# LMS7_FE.net
KiCad netlist of a schematic drawn in Altium Designer
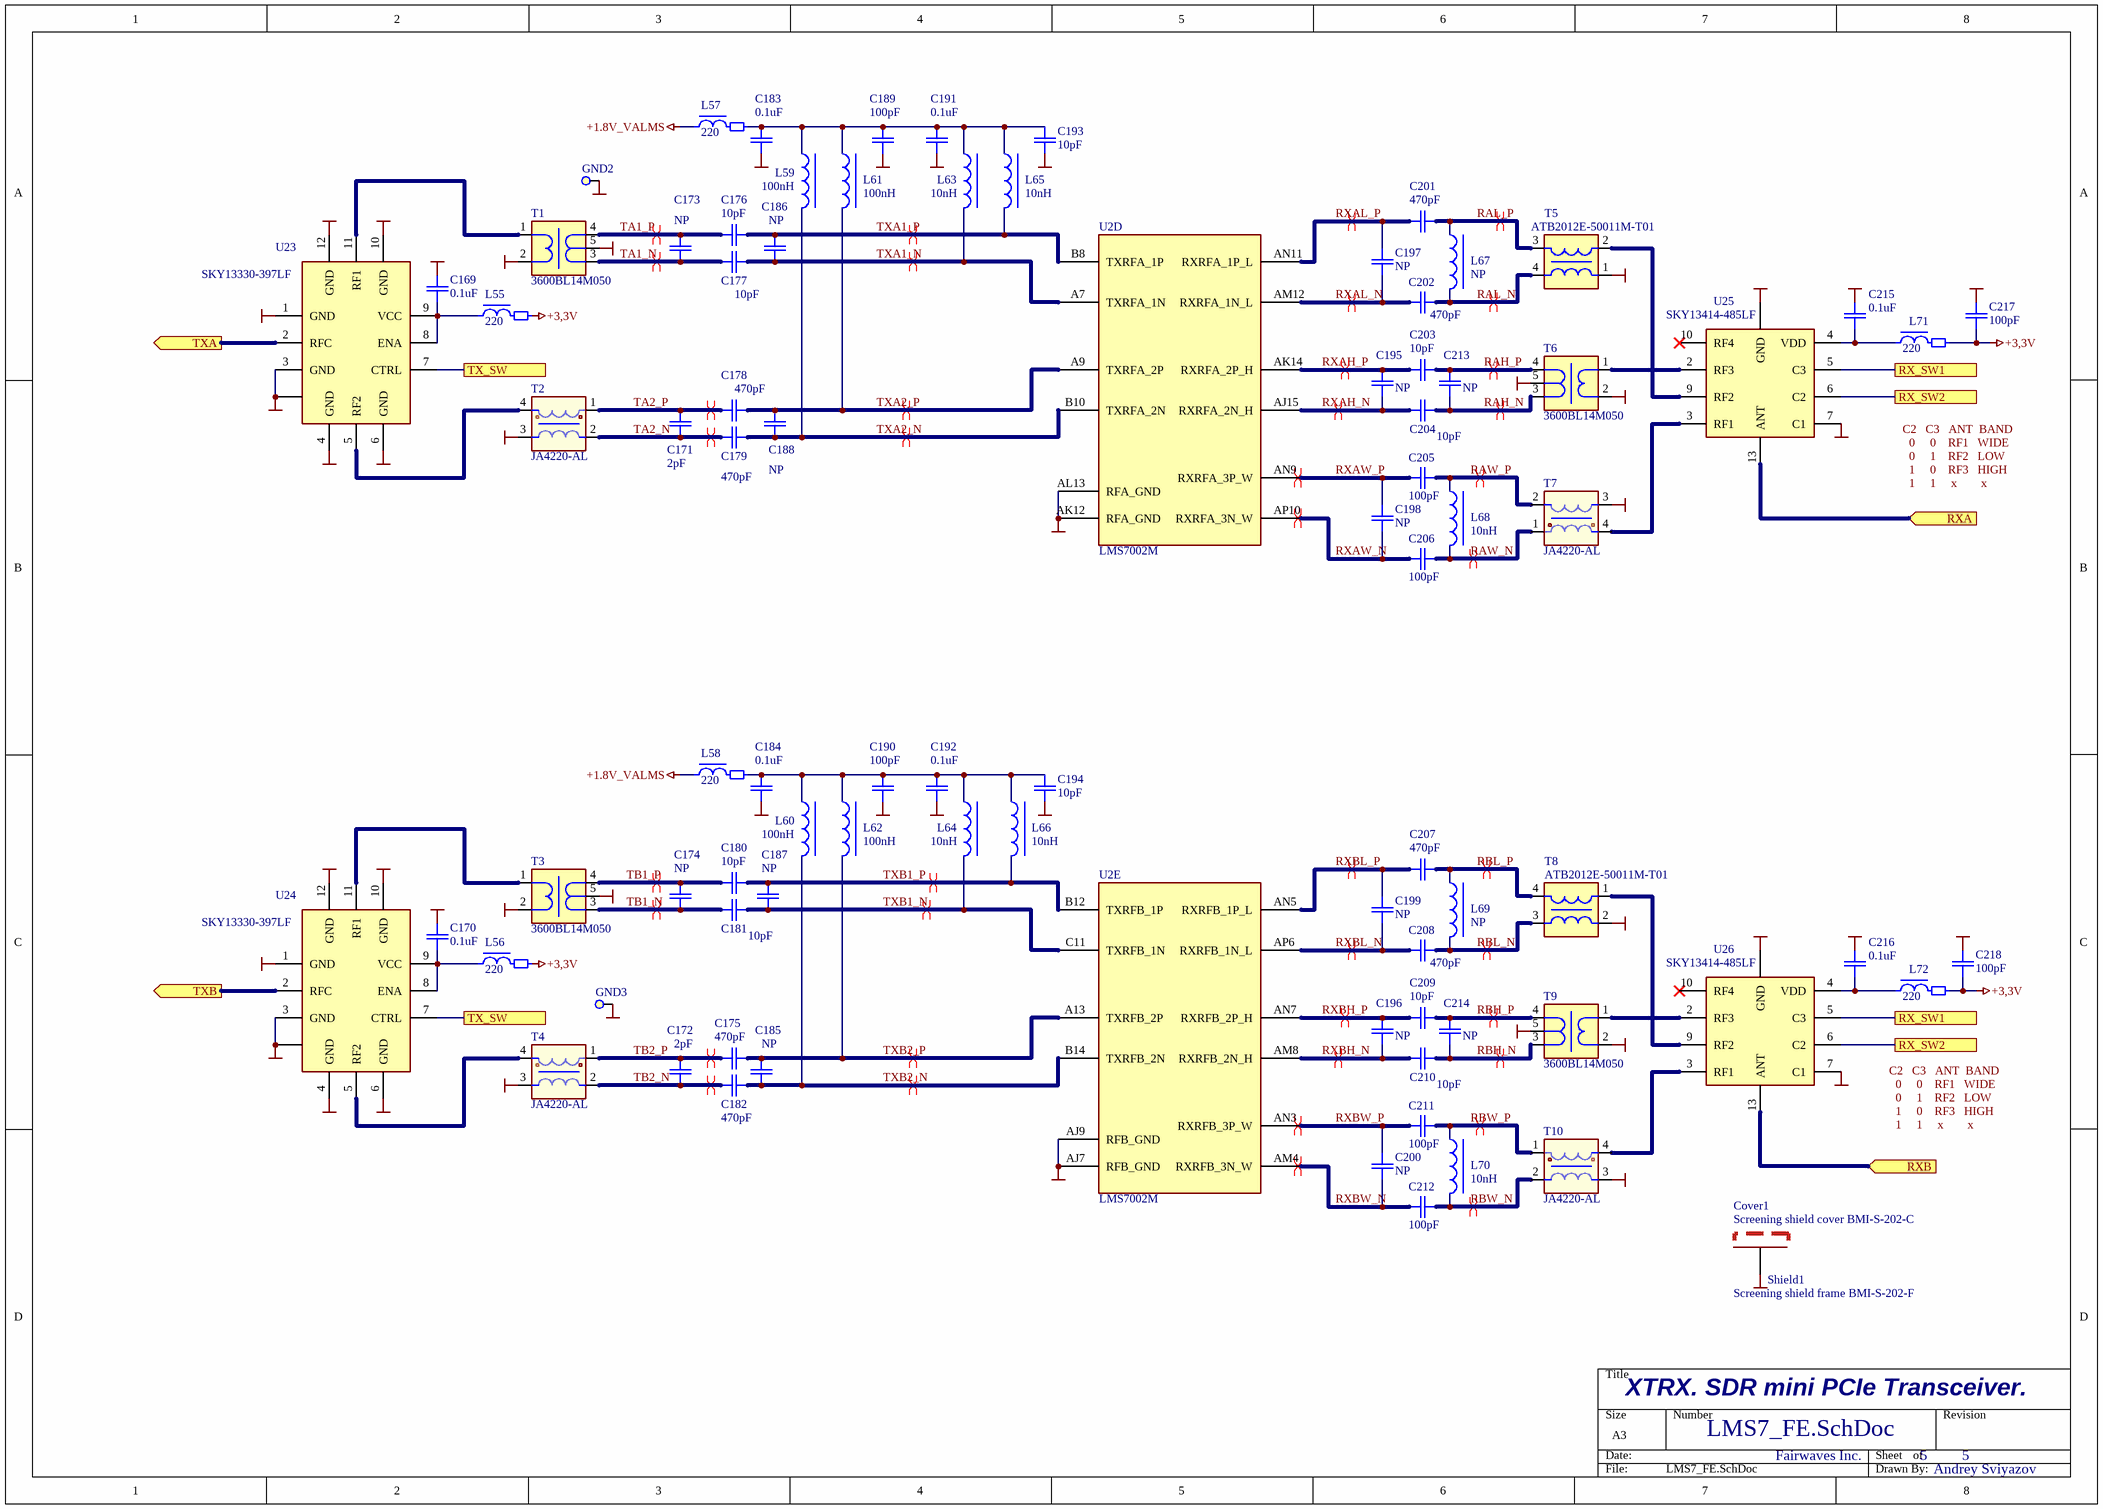
[diagram p0: LMS7_FE.SchDoc]

(export (version "E")
  (design (tool "Eeschema 10.0.6"))
  (components
    (comp (ref "C169")
      (value "0.1uF")
      (footprint "C0402-cirq")
      (description "Capacitor")
      (fields (field (name "MANUFACTURER") "Any") (field (name "TOLERANCE") "20%"))
      (libsource (lib "Capacitors") (part "C0402"))
    )
    (comp (ref "C170")
      (value "0.1uF")
      (footprint "C0402-cirq")
      (description "Capacitor")
      (fields (field (name "MANUFACTURER") "Any") (field (name "TOLERANCE") "20%"))
      (libsource (lib "Capacitors") (part "C0402"))
    )
    (comp (ref "C171")
      (value "2pF")
      (footprint "C0402-cirq")
      (description "Capacitor")
      (fields (field (name "MANUFACTURER") "Any") (field (name "TOLERANCE") "10%"))
      (libsource (lib "Capacitors") (part "C0402"))
    )
    (comp (ref "C172")
      (value "2pF")
      (footprint "C0402-cirq")
      (description "Capacitor")
      (fields (field (name "MANUFACTURER") "Any") (field (name "TOLERANCE") "10%"))
      (libsource (lib "Capacitors") (part "C0402"))
    )
    (comp (ref "C173")
      (value "NP")
      (footprint "C0402-cirq")
      (description "Capacitor")
      (fields (field (name "MANUFACTURER") "MURATA") (field (name "TOLERANCE") "20%"))
      (libsource (lib "Capacitors") (part "C0402"))
    )
    (comp (ref "C174")
      (value "NP")
      (footprint "C0402-cirq")
      (description "Capacitor")
      (fields (field (name "MANUFACTURER") "MURATA") (field (name "TOLERANCE") "20%"))
      (libsource (lib "Capacitors") (part "C0402"))
    )
    (comp (ref "C175")
      (value "470pF")
      (footprint "C0402-cirq")
      (description "Capacitor")
      (fields (field (name "MANUFACTURER") "Any") (field (name "TOLERANCE") "20%"))
      (libsource (lib "Capacitors") (part "C0402"))
    )
    (comp (ref "C176")
      (value "10pF")
      (footprint "C0402-cirq")
      (description "Capacitor")
      (fields (field (name "MANUFACTURER") "Any") (field (name "TOLERANCE") "20%"))
      (libsource (lib "Capacitors") (part "C0402"))
    )
    (comp (ref "C177")
      (value "10pF")
      (footprint "C0402-cirq")
      (description "Capacitor")
      (fields (field (name "MANUFACTURER") "Any") (field (name "TOLERANCE") "20%"))
      (libsource (lib "Capacitors") (part "C0402"))
    )
    (comp (ref "C178")
      (value "470pF")
      (footprint "C0402-cirq")
      (description "Capacitor")
      (fields (field (name "MANUFACTURER") "Any") (field (name "TOLERANCE") "20%"))
      (libsource (lib "Capacitors") (part "C0402"))
    )
    (comp (ref "C179")
      (value "470pF")
      (footprint "C0402-cirq")
      (description "Capacitor")
      (fields (field (name "MANUFACTURER") "Any") (field (name "TOLERANCE") "20%"))
      (libsource (lib "Capacitors") (part "C0402"))
    )
    (comp (ref "C180")
      (value "10pF")
      (footprint "C0402-cirq")
      (description "Capacitor")
      (fields (field (name "MANUFACTURER") "Any") (field (name "TOLERANCE") "20%"))
      (libsource (lib "Capacitors") (part "C0402"))
    )
    (comp (ref "C181")
      (value "10pF")
      (footprint "C0402-cirq")
      (description "Capacitor")
      (fields (field (name "MANUFACTURER") "Any") (field (name "TOLERANCE") "20%"))
      (libsource (lib "Capacitors") (part "C0402"))
    )
    (comp (ref "C182")
      (value "470pF")
      (footprint "C0402-cirq")
      (description "Capacitor")
      (fields (field (name "MANUFACTURER") "Any") (field (name "TOLERANCE") "20%"))
      (libsource (lib "Capacitors") (part "C0402"))
    )
    (comp (ref "C183")
      (value "0.1uF")
      (footprint "C0402-cirq")
      (description "Capacitor")
      (fields (field (name "MANUFACTURER") "Any") (field (name "TOLERANCE") "20%"))
      (libsource (lib "Capacitors") (part "C0402"))
    )
    (comp (ref "C184")
      (value "0.1uF")
      (footprint "C0402-cirq")
      (description "Capacitor")
      (fields (field (name "MANUFACTURER") "Any") (field (name "TOLERANCE") "20%"))
      (libsource (lib "Capacitors") (part "C0402"))
    )
    (comp (ref "C185")
      (value "NP")
      (footprint "C0402-cirq")
      (description "Capacitor")
      (fields (field (name "MANUFACTURER") "MURATA") (field (name "TOLERANCE") "20%"))
      (libsource (lib "Capacitors") (part "C0402"))
    )
    (comp (ref "C186")
      (value "NP")
      (footprint "C0402-cirq")
      (description "Capacitor")
      (fields (field (name "MANUFACTURER") "MURATA") (field (name "TOLERANCE") "20%"))
      (libsource (lib "Capacitors") (part "C0402"))
    )
    (comp (ref "C187")
      (value "NP")
      (footprint "C0402-cirq")
      (description "Capacitor")
      (fields (field (name "MANUFACTURER") "MURATA") (field (name "TOLERANCE") "20%"))
      (libsource (lib "Capacitors") (part "C0402"))
    )
    (comp (ref "C188")
      (value "NP")
      (footprint "C0402-cirq")
      (description "Capacitor")
      (fields (field (name "MANUFACTURER") "MURATA") (field (name "TOLERANCE") "20%"))
      (libsource (lib "Capacitors") (part "C0402"))
    )
    (comp (ref "C189")
      (value "100pF")
      (footprint "C0402-cirq")
      (description "Capacitor")
      (fields (field (name "MANUFACTURER") "Any") (field (name "TOLERANCE") "20%"))
      (libsource (lib "Capacitors") (part "C0402"))
    )
    (comp (ref "C190")
      (value "100pF")
      (footprint "C0402-cirq")
      (description "Capacitor")
      (fields (field (name "MANUFACTURER") "Any") (field (name "TOLERANCE") "20%"))
      (libsource (lib "Capacitors") (part "C0402"))
    )
    (comp (ref "C191")
      (value "0.1uF")
      (footprint "C0402-cirq")
      (description "Capacitor")
      (fields (field (name "MANUFACTURER") "Any") (field (name "TOLERANCE") "20%"))
      (libsource (lib "Capacitors") (part "C0402"))
    )
    (comp (ref "C192")
      (value "0.1uF")
      (footprint "C0402-cirq")
      (description "Capacitor")
      (fields (field (name "MANUFACTURER") "Any") (field (name "TOLERANCE") "20%"))
      (libsource (lib "Capacitors") (part "C0402"))
    )
    (comp (ref "C193")
      (value "10pF")
      (footprint "C0402-cirq")
      (description "Capacitor")
      (fields (field (name "MANUFACTURER") "Any") (field (name "TOLERANCE") "20%"))
      (libsource (lib "Capacitors") (part "C0402"))
    )
    (comp (ref "C194")
      (value "10pF")
      (footprint "C0402-cirq")
      (description "Capacitor")
      (fields (field (name "MANUFACTURER") "Any") (field (name "TOLERANCE") "20%"))
      (libsource (lib "Capacitors") (part "C0402"))
    )
    (comp (ref "C195")
      (value "NP")
      (footprint "C0402-cirq")
      (description "Capacitor")
      (fields (field (name "MANUFACTURER") "MURATA") (field (name "TOLERANCE") "20%"))
      (libsource (lib "Capacitors") (part "C0402"))
    )
    (comp (ref "C196")
      (value "NP")
      (footprint "C0402-cirq")
      (description "Capacitor")
      (fields (field (name "MANUFACTURER") "MURATA") (field (name "TOLERANCE") "20%"))
      (libsource (lib "Capacitors") (part "C0402"))
    )
    (comp (ref "C197")
      (value "NP")
      (footprint "C0402-cirq")
      (description "Capacitor")
      (fields (field (name "MANUFACTURER") "MURATA") (field (name "TOLERANCE") "20%"))
      (libsource (lib "Capacitors") (part "C0402"))
    )
    (comp (ref "C198")
      (value "NP")
      (footprint "C0402-cirq")
      (description "Capacitor")
      (fields (field (name "MANUFACTURER") "MURATA") (field (name "TOLERANCE") "20%"))
      (libsource (lib "Capacitors") (part "C0402"))
    )
    (comp (ref "C199")
      (value "NP")
      (footprint "C0402-cirq")
      (description "Capacitor")
      (fields (field (name "MANUFACTURER") "MURATA") (field (name "TOLERANCE") "20%"))
      (libsource (lib "Capacitors") (part "C0402"))
    )
    (comp (ref "C200")
      (value "NP")
      (footprint "C0402-cirq")
      (description "Capacitor")
      (fields (field (name "MANUFACTURER") "MURATA") (field (name "TOLERANCE") "20%"))
      (libsource (lib "Capacitors") (part "C0402"))
    )
    (comp (ref "C201")
      (value "470pF")
      (footprint "C0402-cirq")
      (description "Capacitor")
      (fields (field (name "MANUFACTURER") "Any") (field (name "TOLERANCE") "20%"))
      (libsource (lib "Capacitors") (part "C0402"))
    )
    (comp (ref "C202")
      (value "470pF")
      (footprint "C0402-cirq")
      (description "Capacitor")
      (fields (field (name "MANUFACTURER") "Any") (field (name "TOLERANCE") "20%"))
      (libsource (lib "Capacitors") (part "C0402"))
    )
    (comp (ref "C203")
      (value "10pF")
      (footprint "C0402-cirq")
      (description "Capacitor")
      (fields (field (name "MANUFACTURER") "Any") (field (name "TOLERANCE") "20%"))
      (libsource (lib "Capacitors") (part "C0402"))
    )
    (comp (ref "C204")
      (value "10pF")
      (footprint "C0402-cirq")
      (description "Capacitor")
      (fields (field (name "MANUFACTURER") "Any") (field (name "TOLERANCE") "20%"))
      (libsource (lib "Capacitors") (part "C0402"))
    )
    (comp (ref "C205")
      (value "100pF")
      (footprint "C0402-cirq")
      (description "Capacitor")
      (fields (field (name "MANUFACTURER") "Any") (field (name "TOLERANCE") "20%"))
      (libsource (lib "Capacitors") (part "C0402"))
    )
    (comp (ref "C206")
      (value "100pF")
      (footprint "C0402-cirq")
      (description "Capacitor")
      (fields (field (name "MANUFACTURER") "Any") (field (name "TOLERANCE") "20%"))
      (libsource (lib "Capacitors") (part "C0402"))
    )
    (comp (ref "C207")
      (value "470pF")
      (footprint "C0402-cirq")
      (description "Capacitor")
      (fields (field (name "MANUFACTURER") "Any") (field (name "TOLERANCE") "20%"))
      (libsource (lib "Capacitors") (part "C0402"))
    )
    (comp (ref "C208")
      (value "470pF")
      (footprint "C0402-cirq")
      (description "Capacitor")
      (fields (field (name "MANUFACTURER") "Any") (field (name "TOLERANCE") "20%"))
      (libsource (lib "Capacitors") (part "C0402"))
    )
    (comp (ref "C209")
      (value "10pF")
      (footprint "C0402-cirq")
      (description "Capacitor")
      (fields (field (name "MANUFACTURER") "Any") (field (name "TOLERANCE") "20%"))
      (libsource (lib "Capacitors") (part "C0402"))
    )
    (comp (ref "C210")
      (value "10pF")
      (footprint "C0402-cirq")
      (description "Capacitor")
      (fields (field (name "MANUFACTURER") "Any") (field (name "TOLERANCE") "20%"))
      (libsource (lib "Capacitors") (part "C0402"))
    )
    (comp (ref "C211")
      (value "100pF")
      (footprint "C0402-cirq")
      (description "Capacitor")
      (fields (field (name "MANUFACTURER") "Any") (field (name "TOLERANCE") "20%"))
      (libsource (lib "Capacitors") (part "C0402"))
    )
    (comp (ref "C212")
      (value "100pF")
      (footprint "C0402-cirq")
      (description "Capacitor")
      (fields (field (name "MANUFACTURER") "Any") (field (name "TOLERANCE") "20%"))
      (libsource (lib "Capacitors") (part "C0402"))
    )
    (comp (ref "C213")
      (value "NP")
      (footprint "C0402-cirq")
      (description "Capacitor")
      (fields (field (name "MANUFACTURER") "MURATA") (field (name "TOLERANCE") "20%"))
      (libsource (lib "Capacitors") (part "C0402"))
    )
    (comp (ref "C214")
      (value "NP")
      (footprint "C0402-cirq")
      (description "Capacitor")
      (fields (field (name "MANUFACTURER") "MURATA") (field (name "TOLERANCE") "20%"))
      (libsource (lib "Capacitors") (part "C0402"))
    )
    (comp (ref "C215")
      (value "0.1uF")
      (footprint "C0402-cirq")
      (description "Capacitor")
      (fields (field (name "MANUFACTURER") "Any") (field (name "TOLERANCE") "20%"))
      (libsource (lib "Capacitors") (part "C0402"))
    )
    (comp (ref "C216")
      (value "0.1uF")
      (footprint "C0402-cirq")
      (description "Capacitor")
      (fields (field (name "MANUFACTURER") "Any") (field (name "TOLERANCE") "20%"))
      (libsource (lib "Capacitors") (part "C0402"))
    )
    (comp (ref "C217")
      (value "100pF")
      (footprint "C0402-cirq")
      (description "Capacitor")
      (fields (field (name "MANUFACTURER") "Any") (field (name "TOLERANCE") "20%"))
      (libsource (lib "Capacitors") (part "C0402"))
    )
    (comp (ref "C218")
      (value "100pF")
      (footprint "C0402-cirq")
      (description "Capacitor")
      (fields (field (name "MANUFACTURER") "Any") (field (name "TOLERANCE") "20%"))
      (libsource (lib "Capacitors") (part "C0402"))
    )
    (comp (ref "Cover1")
      (value "Screening shield cover BMI-S-202-C")
      (description "Screening shield cover")
      (fields (field (name "MANUFACTURER") "Laird Tech"))
      (libsource (lib "Andy") (part "Screen cover BMI-S-202-C"))
    )
    (comp (ref "GND2")
      (value "~")
      (footprint "KP D1.5mm")
      (fields (field (name "MANUFACTURER") "PCB"))
      (libsource (lib "Connectors") (part "KP-D1.5mm"))
    )
    (comp (ref "GND3")
      (value "~")
      (footprint "KP D1.5mm")
      (fields (field (name "MANUFACTURER") "PCB"))
      (libsource (lib "Connectors") (part "KP-D1.5mm"))
    )
    (comp (ref "L55")
      (value "220")
      (footprint "BEAD0402-Phillips")
      (description "Ferrite bead EMIFIL")
      (fields (field (name "MANUFACTURER") "MURATA"))
      (libsource (lib "Andy") (part "EMI BLM15"))
    )
    (comp (ref "L56")
      (value "220")
      (footprint "BEAD0402-Phillips")
      (description "Ferrite bead EMIFIL")
      (fields (field (name "MANUFACTURER") "MURATA"))
      (libsource (lib "Andy") (part "EMI BLM15"))
    )
    (comp (ref "L57")
      (value "220")
      (footprint "BEAD0402-Phillips")
      (description "Ferrite bead EMIFIL")
      (fields (field (name "MANUFACTURER") "MURATA"))
      (libsource (lib "Andy") (part "EMI BLM15"))
    )
    (comp (ref "L58")
      (value "220")
      (footprint "BEAD0402-Phillips")
      (description "Ferrite bead EMIFIL")
      (fields (field (name "MANUFACTURER") "MURATA"))
      (libsource (lib "Andy") (part "EMI BLM15"))
    )
    (comp (ref "L59")
      (value "100nH")
      (footprint "COIL0402-Phillips")
      (description "Coil wire wound")
      (fields (field (name "MANUFACTURER") "MuRata") (field (name "TOLERANCE") "±5%"))
      (libsource (lib "Andy") (part "L-LQW15"))
    )
    (comp (ref "L60")
      (value "100nH")
      (footprint "COIL0402-Phillips")
      (description "Coil wire wound")
      (fields (field (name "MANUFACTURER") "MuRata") (field (name "TOLERANCE") "±5%"))
      (libsource (lib "Andy") (part "L-LQW15"))
    )
    (comp (ref "L61")
      (value "100nH")
      (footprint "COIL0402-Phillips")
      (description "Coil wire wound")
      (fields (field (name "MANUFACTURER") "MuRata") (field (name "TOLERANCE") "±5%"))
      (libsource (lib "Andy") (part "L-LQW15"))
    )
    (comp (ref "L62")
      (value "100nH")
      (footprint "COIL0402-Phillips")
      (description "Coil wire wound")
      (fields (field (name "MANUFACTURER") "MuRata") (field (name "TOLERANCE") "±5%"))
      (libsource (lib "Andy") (part "L-LQW15"))
    )
    (comp (ref "L63")
      (value "10nH")
      (footprint "COIL0402-Phillips")
      (description "Coil wire wound")
      (fields (field (name "MANUFACTURER") "MuRata") (field (name "TOLERANCE") "±5%"))
      (libsource (lib "Andy") (part "L-LQW15"))
    )
    (comp (ref "L64")
      (value "10nH")
      (footprint "COIL0402-Phillips")
      (description "Coil wire wound")
      (fields (field (name "MANUFACTURER") "MuRata") (field (name "TOLERANCE") "±5%"))
      (libsource (lib "Andy") (part "L-LQW15"))
    )
    (comp (ref "L65")
      (value "10nH")
      (footprint "COIL0402-Phillips")
      (description "Coil wire wound")
      (fields (field (name "MANUFACTURER") "MuRata") (field (name "TOLERANCE") "±5%"))
      (libsource (lib "Andy") (part "L-LQW15"))
    )
    (comp (ref "L66")
      (value "10nH")
      (footprint "COIL0402-Phillips")
      (description "Coil wire wound")
      (fields (field (name "MANUFACTURER") "MuRata") (field (name "TOLERANCE") "±5%"))
      (libsource (lib "Andy") (part "L-LQW15"))
    )
    (comp (ref "L67")
      (value "NP")
      (footprint "COIL0402-Phillips")
      (description "Coil wire wound")
      (fields (field (name "MANUFACTURER") "MuRata") (field (name "TOLERANCE") "±5%"))
      (libsource (lib "Andy") (part "L-LQW15"))
    )
    (comp (ref "L68")
      (value "10nH")
      (footprint "COIL0402-Phillips")
      (description "Coil wire wound")
      (fields (field (name "MANUFACTURER") "MuRata") (field (name "TOLERANCE") "±5%"))
      (libsource (lib "Andy") (part "L-LQW15"))
    )
    (comp (ref "L69")
      (value "NP")
      (footprint "COIL0402-Phillips")
      (description "Coil wire wound")
      (fields (field (name "MANUFACTURER") "MuRata") (field (name "TOLERANCE") "±5%"))
      (libsource (lib "Andy") (part "L-LQW15"))
    )
    (comp (ref "L70")
      (value "10nH")
      (footprint "COIL0402-Phillips")
      (description "Coil wire wound")
      (fields (field (name "MANUFACTURER") "MuRata") (field (name "TOLERANCE") "±5%"))
      (libsource (lib "Andy") (part "L-LQW15"))
    )
    (comp (ref "L71")
      (value "220")
      (footprint "BEAD0402-Phillips")
      (description "Ferrite bead EMIFIL")
      (fields (field (name "MANUFACTURER") "MURATA"))
      (libsource (lib "Andy") (part "EMI BLM15"))
    )
    (comp (ref "L72")
      (value "220")
      (footprint "BEAD0402-Phillips")
      (description "Ferrite bead EMIFIL")
      (fields (field (name "MANUFACTURER") "MURATA"))
      (libsource (lib "Andy") (part "EMI BLM15"))
    )
    (comp (ref "Shield1")
      (value "Screening shield frame BMI-S-202-F")
      (footprint "BMI-S-202-F")
      (description "Screening shield frame")
      (fields (field (name "MANUFACTURER") "Laird Tech"))
      (libsource (lib "Andy") (part "Screen frame BMI-S-202-F"))
    )
    (comp (ref "T1")
      (value "3600BL14M050")
      (footprint "Balun 1.6x0.8x0.6mm")
      (description "Balun bal-unbal")
      (fields (field (name "MANUFACTURER") "Johanson Technology, Inc."))
      (libsource (lib "Andy") (part "Balun 3-4GHz"))
    )
    (comp (ref "T2")
      (value "JA4220-AL")
      (footprint "JA4220-AL")
      (description "Balun")
      (fields (field (name "MANUFACTURER") "Coilcraft"))
      (libsource (lib "Andy") (part "Balun JA4220-AL"))
    )
    (comp (ref "T3")
      (value "3600BL14M050")
      (footprint "Balun 1.6x0.8x0.6mm")
      (description "Balun bal-unbal")
      (fields (field (name "MANUFACTURER") "Johanson Technology, Inc."))
      (libsource (lib "Andy") (part "Balun 3-4GHz"))
    )
    (comp (ref "T4")
      (value "JA4220-AL")
      (footprint "JA4220-AL")
      (description "Balun")
      (fields (field (name "MANUFACTURER") "Coilcraft"))
      (libsource (lib "Andy") (part "Balun JA4220-AL"))
    )
    (comp (ref "T5")
      (value "ATB2012E-50011M-T01")
      (footprint "Balun 1.2x2x1mm")
      (description "Balun bal-unbal")
      (fields (field (name "MANUFACTURER") "TDK"))
      (libsource (lib "") (part "Balun ATB2012_1"))
    )
    (comp (ref "T6")
      (value "3600BL14M050")
      (footprint "Balun 1.6x0.8x0.6mm")
      (description "Balun bal-unbal")
      (fields (field (name "MANUFACTURER") "Johanson Technology, Inc."))
      (libsource (lib "") (part "Balun 3-4GHz_1"))
    )
    (comp (ref "T7")
      (value "JA4220-AL")
      (footprint "JA4220-AL")
      (description "Balun")
      (fields (field (name "MANUFACTURER") "Coilcraft"))
      (libsource (lib "") (part "Balun JA4220-AL_1"))
    )
    (comp (ref "T8")
      (value "ATB2012E-50011M-T01")
      (footprint "Balun 1.2x2x1mm")
      (description "Balun bal-unbal")
      (fields (field (name "MANUFACTURER") "TDK"))
      (libsource (lib "Andy") (part "Balun ATB2012"))
    )
    (comp (ref "T9")
      (value "3600BL14M050")
      (footprint "Balun 1.6x0.8x0.6mm")
      (description "Balun bal-unbal")
      (fields (field (name "MANUFACTURER") "Johanson Technology, Inc."))
      (libsource (lib "") (part "Balun 3-4GHz_1"))
    )
    (comp (ref "T10")
      (value "JA4220-AL")
      (footprint "JA4220-AL")
      (description "Balun")
      (fields (field (name "MANUFACTURER") "Coilcraft"))
      (libsource (lib "") (part "Balun JA4220-AL_2"))
    )
    (comp (ref "U2")
      (value "LMS7002M")
      (footprint "Andy:aQFN260(11.5x11.5mm)")
      (description "IC FPRF MIMO Transceiver")
      (fields (field (name "MANUFACTURER") "Lime Microsystems"))
      (libsource (lib "Andy") (part "LMS7002M"))
    )
    (comp (ref "U23")
      (value "SKY13330-397LF")
      (footprint "QFN12(2x2/0.5)")
      (description "IC RF Switch")
      (fields (field (name "MANUFACTURER") "Skyworks"))
      (libsource (lib "Andy") (part "SKY13330-397LF"))
    )
    (comp (ref "U24")
      (value "SKY13330-397LF")
      (footprint "QFN12(2x2/0.5)")
      (description "IC RF Switch")
      (fields (field (name "MANUFACTURER") "Skyworks"))
      (libsource (lib "Andy") (part "SKY13330-397LF"))
    )
    (comp (ref "U25")
      (value "SKY13414-485LF")
      (footprint "QFN14(2x2/0.4-0.45)")
      (description "IC RF SP4T Switch")
      (fields (field (name "MANUFACTURER") "Skyworks"))
      (libsource (lib "Andy") (part "SKY13414-485LF"))
    )
    (comp (ref "U26")
      (value "SKY13414-485LF")
      (footprint "QFN14(2x2/0.4-0.45)")
      (description "IC RF SP4T Switch")
      (fields (field (name "MANUFACTURER") "Skyworks"))
      (libsource (lib "Andy") (part "SKY13414-485LF"))
    )
  )
  (nets
    (net (code "1") (name "+1.8V_VALMS") (class "Default")
      (node (ref "L57") (pin "1") (pinfunction "1_1") (pintype "passive"))
      (node (ref "L58") (pin "1") (pinfunction "1_1") (pintype "passive"))
    )
    (net (code "2") (name "+3,3V") (class "Default")
      (node (ref "C217") (pin "1") (pinfunction "1_1") (pintype "passive"))
      (node (ref "C218") (pin "1") (pinfunction "1_1") (pintype "passive"))
      (node (ref "L55") (pin "2") (pinfunction "2_2") (pintype "passive"))
      (node (ref "L56") (pin "2") (pinfunction "2_2") (pintype "passive"))
      (node (ref "L71") (pin "2") (pinfunction "2_2") (pintype "passive"))
      (node (ref "L72") (pin "2") (pinfunction "2_2") (pintype "passive"))
    )
    (net (code "3") (name "/RAH_N") (class "Default")
      (node (ref "C204") (pin "2") (pinfunction "2_2") (pintype "passive"))
      (node (ref "C213") (pin "1") (pinfunction "1_1") (pintype "passive"))
      (node (ref "T6") (pin "3") (pinfunction "3_3") (pintype "passive"))
    )
    (net (code "4") (name "/RAH_P") (class "Default")
      (node (ref "C203") (pin "2") (pinfunction "2_2") (pintype "passive"))
      (node (ref "C213") (pin "2") (pinfunction "2_2") (pintype "passive"))
      (node (ref "T6") (pin "4") (pinfunction "4_4") (pintype "passive"))
    )
    (net (code "5") (name "/RAL_N") (class "Default")
      (node (ref "C202") (pin "1") (pinfunction "1_1") (pintype "passive"))
      (node (ref "L67") (pin "2") (pinfunction "2_2") (pintype "passive"))
      (node (ref "T5") (pin "4") (pinfunction "4_4") (pintype "passive"))
    )
    (net (code "6") (name "/RAL_P") (class "Default")
      (node (ref "C201") (pin "1") (pinfunction "1_1") (pintype "passive"))
      (node (ref "L67") (pin "1") (pinfunction "1_1") (pintype "passive"))
      (node (ref "T5") (pin "3") (pinfunction "3_3") (pintype "passive"))
    )
    (net (code "7") (name "/RAW_N") (class "Default")
      (node (ref "C206") (pin "2") (pinfunction "2_2") (pintype "passive"))
      (node (ref "L68") (pin "2") (pinfunction "2_2") (pintype "passive"))
      (node (ref "T7") (pin "1") (pinfunction "Sec_1") (pintype "passive"))
    )
    (net (code "8") (name "/RAW_P") (class "Default")
      (node (ref "C205") (pin "2") (pinfunction "2_2") (pintype "passive"))
      (node (ref "L68") (pin "1") (pinfunction "1_1") (pintype "passive"))
      (node (ref "T7") (pin "2") (pinfunction "Sec_Dot_2") (pintype "passive"))
    )
    (net (code "9") (name "/RBH_N") (class "Default")
      (node (ref "C210") (pin "2") (pinfunction "2_2") (pintype "passive"))
      (node (ref "C214") (pin "1") (pinfunction "1_1") (pintype "passive"))
      (node (ref "T9") (pin "3") (pinfunction "3_3") (pintype "passive"))
    )
    (net (code "10") (name "/RBH_P") (class "Default")
      (node (ref "C209") (pin "2") (pinfunction "2_2") (pintype "passive"))
      (node (ref "C214") (pin "2") (pinfunction "2_2") (pintype "passive"))
      (node (ref "T9") (pin "4") (pinfunction "4_4") (pintype "passive"))
    )
    (net (code "11") (name "/RBL_N") (class "Default")
      (node (ref "C208") (pin "1") (pinfunction "1_1") (pintype "passive"))
      (node (ref "L69") (pin "2") (pinfunction "2_2") (pintype "passive"))
      (node (ref "T8") (pin "3") (pinfunction "3_3") (pintype "passive"))
    )
    (net (code "12") (name "/RBL_P") (class "Default")
      (node (ref "C207") (pin "1") (pinfunction "1_1") (pintype "passive"))
      (node (ref "L69") (pin "1") (pinfunction "1_1") (pintype "passive"))
      (node (ref "T8") (pin "4") (pinfunction "4_4") (pintype "passive"))
    )
    (net (code "13") (name "/RBW_N") (class "Default")
      (node (ref "C212") (pin "2") (pinfunction "2_2") (pintype "passive"))
      (node (ref "L70") (pin "2") (pinfunction "2_2") (pintype "passive"))
      (node (ref "T10") (pin "2") (pinfunction "Sec_Dot_2") (pintype "passive"))
    )
    (net (code "14") (name "/RBW_P") (class "Default")
      (node (ref "C211") (pin "2") (pinfunction "2_2") (pintype "passive"))
      (node (ref "L70") (pin "1") (pinfunction "1_1") (pintype "passive"))
      (node (ref "T10") (pin "1") (pinfunction "Sec_1") (pintype "passive"))
    )
    (net (code "15") (name "/RXA") (class "Default")
      (node (ref "U25") (pin "13") (pinfunction "ANT_13") (pintype "passive"))
    )
    (net (code "16") (name "/RXAH_N") (class "Default")
      (node (ref "C195") (pin "1") (pinfunction "1_1") (pintype "passive"))
      (node (ref "C204") (pin "1") (pinfunction "1_1") (pintype "passive"))
      (node (ref "U2") (pin "AJ15") (pinfunction "RXRFA_2N_H_AJ15") (pintype "passive"))
    )
    (net (code "17") (name "/RXAH_P") (class "Default")
      (node (ref "C195") (pin "2") (pinfunction "2_2") (pintype "passive"))
      (node (ref "C203") (pin "1") (pinfunction "1_1") (pintype "passive"))
      (node (ref "U2") (pin "AK14") (pinfunction "RXRFA_2P_H_AK14") (pintype "passive"))
    )
    (net (code "18") (name "/RXAL_N") (class "Default")
      (node (ref "C197") (pin "1") (pinfunction "1_1") (pintype "passive"))
      (node (ref "C202") (pin "2") (pinfunction "2_2") (pintype "passive"))
      (node (ref "U2") (pin "AM12") (pinfunction "RXRFA_1N_L_AM12") (pintype "passive"))
    )
    (net (code "19") (name "/RXAL_P") (class "Default")
      (node (ref "C197") (pin "2") (pinfunction "2_2") (pintype "passive"))
      (node (ref "C201") (pin "2") (pinfunction "2_2") (pintype "passive"))
      (node (ref "U2") (pin "AN11") (pinfunction "RXRFA_1P_L_AN11") (pintype "passive"))
    )
    (net (code "20") (name "/RXAW_N") (class "Default")
      (node (ref "C198") (pin "1") (pinfunction "1_1") (pintype "passive"))
      (node (ref "C206") (pin "1") (pinfunction "1_1") (pintype "passive"))
      (node (ref "U2") (pin "AP10") (pinfunction "RXRFA_3N_W_AP10") (pintype "passive"))
    )
    (net (code "21") (name "/RXAW_P") (class "Default")
      (node (ref "C198") (pin "2") (pinfunction "2_2") (pintype "passive"))
      (node (ref "C205") (pin "1") (pinfunction "1_1") (pintype "passive"))
      (node (ref "U2") (pin "AN9") (pinfunction "RXRFA_3P_W_AN9") (pintype "passive"))
    )
    (net (code "22") (name "/RXB") (class "Default")
      (node (ref "U26") (pin "13") (pinfunction "ANT_13") (pintype "passive"))
    )
    (net (code "23") (name "/RXBH_N") (class "Default")
      (node (ref "C196") (pin "1") (pinfunction "1_1") (pintype "passive"))
      (node (ref "C210") (pin "1") (pinfunction "1_1") (pintype "passive"))
      (node (ref "U2") (pin "AM8") (pinfunction "RXRFB_2N_H_AM8") (pintype "passive"))
    )
    (net (code "24") (name "/RXBH_P") (class "Default")
      (node (ref "C196") (pin "2") (pinfunction "2_2") (pintype "passive"))
      (node (ref "C209") (pin "1") (pinfunction "1_1") (pintype "passive"))
      (node (ref "U2") (pin "AN7") (pinfunction "RXRFB_2P_H_AN7") (pintype "passive"))
    )
    (net (code "25") (name "/RXBL_N") (class "Default")
      (node (ref "C199") (pin "1") (pinfunction "1_1") (pintype "passive"))
      (node (ref "C208") (pin "2") (pinfunction "2_2") (pintype "passive"))
      (node (ref "U2") (pin "AP6") (pinfunction "RXRFB_1N_L_AP6") (pintype "passive"))
    )
    (net (code "26") (name "/RXBL_P") (class "Default")
      (node (ref "C199") (pin "2") (pinfunction "2_2") (pintype "passive"))
      (node (ref "C207") (pin "2") (pinfunction "2_2") (pintype "passive"))
      (node (ref "U2") (pin "AN5") (pinfunction "RXRFB_1P_L_AN5") (pintype "passive"))
    )
    (net (code "27") (name "/RXBW_N") (class "Default")
      (node (ref "C200") (pin "2") (pinfunction "2_2") (pintype "passive"))
      (node (ref "C212") (pin "1") (pinfunction "1_1") (pintype "passive"))
      (node (ref "U2") (pin "AM4") (pinfunction "RXRFB_3N_W_AM4") (pintype "passive"))
    )
    (net (code "28") (name "/RXBW_P") (class "Default")
      (node (ref "C200") (pin "1") (pinfunction "1_1") (pintype "passive"))
      (node (ref "C211") (pin "1") (pinfunction "1_1") (pintype "passive"))
      (node (ref "U2") (pin "AN3") (pinfunction "RXRFB_3P_W_AN3") (pintype "passive"))
    )
    (net (code "29") (name "/RX_SW1") (class "Default")
      (node (ref "U25") (pin "5") (pinfunction "C3_5") (pintype "passive"))
      (node (ref "U26") (pin "5") (pinfunction "C3_5") (pintype "passive"))
    )
    (net (code "30") (name "/RX_SW2") (class "Default")
      (node (ref "U25") (pin "6") (pinfunction "C2_6") (pintype "passive"))
      (node (ref "U26") (pin "6") (pinfunction "C2_6") (pintype "passive"))
    )
    (net (code "31") (name "/TA1_N") (class "Default")
      (node (ref "C173") (pin "2") (pinfunction "2_2") (pintype "passive"))
      (node (ref "C177") (pin "1") (pinfunction "1_1") (pintype "passive"))
      (node (ref "T1") (pin "3") (pinfunction "3_3") (pintype "passive"))
    )
    (net (code "32") (name "/TA1_P") (class "Default")
      (node (ref "C173") (pin "1") (pinfunction "1_1") (pintype "passive"))
      (node (ref "C176") (pin "1") (pinfunction "1_1") (pintype "passive"))
      (node (ref "T1") (pin "4") (pinfunction "4_4") (pintype "passive"))
    )
    (net (code "33") (name "/TA2_N") (class "Default")
      (node (ref "C171") (pin "2") (pinfunction "2_2") (pintype "passive"))
      (node (ref "C179") (pin "2") (pinfunction "2_2") (pintype "passive"))
      (node (ref "T2") (pin "2") (pinfunction "Sec_Dot_2") (pintype "passive"))
    )
    (net (code "34") (name "/TA2_P") (class "Default")
      (node (ref "C171") (pin "1") (pinfunction "1_1") (pintype "passive"))
      (node (ref "C178") (pin "2") (pinfunction "2_2") (pintype "passive"))
      (node (ref "T2") (pin "1") (pinfunction "Sec_1") (pintype "passive"))
    )
    (net (code "35") (name "/TB1_N") (class "Default")
      (node (ref "C174") (pin "1") (pinfunction "1_1") (pintype "passive"))
      (node (ref "C181") (pin "1") (pinfunction "1_1") (pintype "passive"))
      (node (ref "T3") (pin "3") (pinfunction "3_3") (pintype "passive"))
    )
    (net (code "36") (name "/TB1_P") (class "Default")
      (node (ref "C174") (pin "2") (pinfunction "2_2") (pintype "passive"))
      (node (ref "C180") (pin "1") (pinfunction "1_1") (pintype "passive"))
      (node (ref "T3") (pin "4") (pinfunction "4_4") (pintype "passive"))
    )
    (net (code "37") (name "/TB2_N") (class "Default")
      (node (ref "C172") (pin "1") (pinfunction "1_1") (pintype "passive"))
      (node (ref "C182") (pin "2") (pinfunction "2_2") (pintype "passive"))
      (node (ref "T4") (pin "2") (pinfunction "Sec_Dot_2") (pintype "passive"))
    )
    (net (code "38") (name "/TB2_P") (class "Default")
      (node (ref "C172") (pin "2") (pinfunction "2_2") (pintype "passive"))
      (node (ref "C175") (pin "2") (pinfunction "2_2") (pintype "passive"))
      (node (ref "T4") (pin "1") (pinfunction "Sec_1") (pintype "passive"))
    )
    (net (code "39") (name "/TXA") (class "Default")
      (node (ref "U23") (pin "2") (pinfunction "RFC_2") (pintype "passive"))
    )
    (net (code "40") (name "/TXA1_N") (class "Default")
      (node (ref "C177") (pin "2") (pinfunction "2_2") (pintype "passive"))
      (node (ref "C186") (pin "2") (pinfunction "2_2") (pintype "passive"))
      (node (ref "L63") (pin "2") (pinfunction "2_2") (pintype "passive"))
      (node (ref "U2") (pin "A7") (pinfunction "TXRFA_1N_A7") (pintype "passive"))
    )
    (net (code "41") (name "/TXA1_P") (class "Default")
      (node (ref "C176") (pin "2") (pinfunction "2_2") (pintype "passive"))
      (node (ref "C186") (pin "1") (pinfunction "1_1") (pintype "passive"))
      (node (ref "L65") (pin "2") (pinfunction "2_2") (pintype "passive"))
      (node (ref "U2") (pin "B8") (pinfunction "TXRFA_1P_B8") (pintype "passive"))
    )
    (net (code "42") (name "/TXA2_N") (class "Default")
      (node (ref "C179") (pin "1") (pinfunction "1_1") (pintype "passive"))
      (node (ref "C188") (pin "2") (pinfunction "2_2") (pintype "passive"))
      (node (ref "L59") (pin "2") (pinfunction "2_2") (pintype "passive"))
      (node (ref "U2") (pin "B10") (pinfunction "TXRFA_2N_B10") (pintype "passive"))
    )
    (net (code "43") (name "/TXA2_P") (class "Default")
      (node (ref "C178") (pin "1") (pinfunction "1_1") (pintype "passive"))
      (node (ref "C188") (pin "1") (pinfunction "1_1") (pintype "passive"))
      (node (ref "L61") (pin "2") (pinfunction "2_2") (pintype "passive"))
      (node (ref "U2") (pin "A9") (pinfunction "TXRFA_2P_A9") (pintype "passive"))
    )
    (net (code "44") (name "/TXB") (class "Default")
      (node (ref "U24") (pin "2") (pinfunction "RFC_2") (pintype "passive"))
    )
    (net (code "45") (name "/TXB1_N") (class "Default")
      (node (ref "C181") (pin "2") (pinfunction "2_2") (pintype "passive"))
      (node (ref "C187") (pin "1") (pinfunction "1_1") (pintype "passive"))
      (node (ref "L64") (pin "2") (pinfunction "2_2") (pintype "passive"))
      (node (ref "U2") (pin "C11") (pinfunction "TXRFB_1N_C11") (pintype "passive"))
    )
    (net (code "46") (name "/TXB1_P") (class "Default")
      (node (ref "C180") (pin "2") (pinfunction "2_2") (pintype "passive"))
      (node (ref "C187") (pin "2") (pinfunction "2_2") (pintype "passive"))
      (node (ref "L66") (pin "2") (pinfunction "2_2") (pintype "passive"))
      (node (ref "U2") (pin "B12") (pinfunction "TXRFB_1P_B12") (pintype "passive"))
    )
    (net (code "47") (name "/TXB2_N") (class "Default")
      (node (ref "C182") (pin "1") (pinfunction "1_1") (pintype "passive"))
      (node (ref "C185") (pin "1") (pinfunction "1_1") (pintype "passive"))
      (node (ref "L60") (pin "2") (pinfunction "2_2") (pintype "passive"))
      (node (ref "U2") (pin "B14") (pinfunction "TXRFB_2N_B14") (pintype "passive"))
    )
    (net (code "48") (name "/TXB2_P") (class "Default")
      (node (ref "C175") (pin "1") (pinfunction "1_1") (pintype "passive"))
      (node (ref "C185") (pin "2") (pinfunction "2_2") (pintype "passive"))
      (node (ref "L62") (pin "2") (pinfunction "2_2") (pintype "passive"))
      (node (ref "U2") (pin "A13") (pinfunction "TXRFB_2P_A13") (pintype "passive"))
    )
    (net (code "49") (name "/TX_SW") (class "Default")
      (node (ref "U23") (pin "7") (pinfunction "CTRL_7") (pintype "passive"))
      (node (ref "U24") (pin "7") (pinfunction "CTRL_7") (pintype "passive"))
    )
    (net (code "50") (name "GND") (class "Default")
      (node (ref "C169") (pin "2") (pinfunction "2_2") (pintype "passive"))
      (node (ref "C170") (pin "2") (pinfunction "2_2") (pintype "passive"))
      (node (ref "C183") (pin "2") (pinfunction "2_2") (pintype "passive"))
      (node (ref "C184") (pin "2") (pinfunction "2_2") (pintype "passive"))
      (node (ref "C189") (pin "2") (pinfunction "2_2") (pintype "passive"))
      (node (ref "C190") (pin "2") (pinfunction "2_2") (pintype "passive"))
      (node (ref "C191") (pin "2") (pinfunction "2_2") (pintype "passive"))
      (node (ref "C192") (pin "2") (pinfunction "2_2") (pintype "passive"))
      (node (ref "C193") (pin "1") (pinfunction "1_1") (pintype "passive"))
      (node (ref "C194") (pin "1") (pinfunction "1_1") (pintype "passive"))
      (node (ref "C215") (pin "1") (pinfunction "1_1") (pintype "passive"))
      (node (ref "C216") (pin "1") (pinfunction "1_1") (pintype "passive"))
      (node (ref "C217") (pin "2") (pinfunction "2_2") (pintype "passive"))
      (node (ref "C218") (pin "2") (pinfunction "2_2") (pintype "passive"))
      (node (ref "GND2") (pin "1") (pinfunction "1_1") (pintype "passive"))
      (node (ref "GND3") (pin "1") (pinfunction "1_1") (pintype "passive"))
      (node (ref "Shield1") (pin "0") (pinfunction "GND_0") (pintype "passive"))
      (node (ref "T1") (pin "2") (pinfunction "2_2") (pintype "passive"))
      (node (ref "T1") (pin "5") (pinfunction "5_5") (pintype "passive"))
      (node (ref "T10") (pin "3") (pinfunction "Pri_3") (pintype "passive"))
      (node (ref "T2") (pin "3") (pinfunction "Pri_3") (pintype "passive"))
      (node (ref "T3") (pin "2") (pinfunction "2_2") (pintype "passive"))
      (node (ref "T3") (pin "5") (pinfunction "5_5") (pintype "passive"))
      (node (ref "T4") (pin "3") (pinfunction "Pri_3") (pintype "passive"))
      (node (ref "T5") (pin "1") (pinfunction "1_1") (pintype "passive"))
      (node (ref "T6") (pin "2") (pinfunction "2_2") (pintype "passive"))
      (node (ref "T6") (pin "5") (pinfunction "5_5") (pintype "passive"))
      (node (ref "T7") (pin "3") (pinfunction "Pri_3") (pintype "passive"))
      (node (ref "T8") (pin "2") (pinfunction "2_2") (pintype "passive"))
      (node (ref "T9") (pin "2") (pinfunction "2_2") (pintype "passive"))
      (node (ref "T9") (pin "5") (pinfunction "5_5") (pintype "passive"))
      (node (ref "U2") (pin "AJ7") (pinfunction "RFB_GND_AJ7") (pintype "passive"))
      (node (ref "U2") (pin "AJ9") (pinfunction "RFB_GND_AJ9") (pintype "passive"))
      (node (ref "U2") (pin "AK12") (pinfunction "RFA_GND_AK12") (pintype "passive"))
      (node (ref "U2") (pin "AL13") (pinfunction "RFA_GND_AL13") (pintype "passive"))
      (node (ref "U23") (pin "0") (pintype "passive"))
      (node (ref "U23") (pin "1") (pinfunction "GND_1") (pintype "passive"))
      (node (ref "U23") (pin "10") (pinfunction "GND_10") (pintype "passive"))
      (node (ref "U23") (pin "12") (pinfunction "GND_12") (pintype "passive"))
      (node (ref "U23") (pin "3") (pinfunction "GND_3") (pintype "passive"))
      (node (ref "U23") (pin "4") (pinfunction "GND_4") (pintype "passive"))
      (node (ref "U23") (pin "6") (pinfunction "GND_6") (pintype "passive"))
      (node (ref "U24") (pin "0") (pintype "passive"))
      (node (ref "U24") (pin "1") (pinfunction "GND_1") (pintype "passive"))
      (node (ref "U24") (pin "10") (pinfunction "GND_10") (pintype "passive"))
      (node (ref "U24") (pin "12") (pinfunction "GND_12") (pintype "passive"))
      (node (ref "U24") (pin "3") (pinfunction "GND_3") (pintype "passive"))
      (node (ref "U24") (pin "4") (pinfunction "GND_4") (pintype "passive"))
      (node (ref "U24") (pin "6") (pinfunction "GND_6") (pintype "passive"))
      (node (ref "U25") (pin "0") (pinfunction "GND_0") (pintype "passive"))
      (node (ref "U25") (pin "7") (pinfunction "C1_7") (pintype "passive"))
      (node (ref "U26") (pin "0") (pinfunction "GND_0") (pintype "passive"))
      (node (ref "U26") (pin "7") (pinfunction "C1_7") (pintype "passive"))
    )
    (net (code "51") (name "Net-(C183-Pad1)") (class "Default")
      (node (ref "C183") (pin "1") (pinfunction "1_1") (pintype "passive"))
      (node (ref "C189") (pin "1") (pinfunction "1_1") (pintype "passive"))
      (node (ref "C191") (pin "1") (pinfunction "1_1") (pintype "passive"))
      (node (ref "C193") (pin "2") (pinfunction "2_2") (pintype "passive"))
      (node (ref "L57") (pin "2") (pinfunction "2_2") (pintype "passive"))
      (node (ref "L59") (pin "1") (pinfunction "1_1") (pintype "passive"))
      (node (ref "L61") (pin "1") (pinfunction "1_1") (pintype "passive"))
      (node (ref "L63") (pin "1") (pinfunction "1_1") (pintype "passive"))
      (node (ref "L65") (pin "1") (pinfunction "1_1") (pintype "passive"))
    )
    (net (code "52") (name "Net-(C184-Pad1)") (class "Default")
      (node (ref "C184") (pin "1") (pinfunction "1_1") (pintype "passive"))
      (node (ref "C190") (pin "1") (pinfunction "1_1") (pintype "passive"))
      (node (ref "C192") (pin "1") (pinfunction "1_1") (pintype "passive"))
      (node (ref "C194") (pin "2") (pinfunction "2_2") (pintype "passive"))
      (node (ref "L58") (pin "2") (pinfunction "2_2") (pintype "passive"))
      (node (ref "L60") (pin "1") (pinfunction "1_1") (pintype "passive"))
      (node (ref "L62") (pin "1") (pinfunction "1_1") (pintype "passive"))
      (node (ref "L64") (pin "1") (pinfunction "1_1") (pintype "passive"))
      (node (ref "L66") (pin "1") (pinfunction "1_1") (pintype "passive"))
    )
    (net (code "53") (name "Net-(T2-Pri_Dot)") (class "Default")
      (node (ref "T2") (pin "4") (pinfunction "Pri_Dot_4") (pintype "passive"))
      (node (ref "U23") (pin "5") (pinfunction "RF2_5") (pintype "passive"))
    )
    (net (code "54") (name "Net-(T4-Pri_Dot)") (class "Default")
      (node (ref "T4") (pin "4") (pinfunction "Pri_Dot_4") (pintype "passive"))
      (node (ref "U24") (pin "5") (pinfunction "RF2_5") (pintype "passive"))
    )
    (net (code "55") (name "Net-(T7-Pri_Dot)") (class "Default")
      (node (ref "T7") (pin "4") (pinfunction "Pri_Dot_4") (pintype "passive"))
      (node (ref "U25") (pin "3") (pinfunction "RF1_3") (pintype "passive"))
    )
    (net (code "56") (name "Net-(T10-Pri_Dot)") (class "Default")
      (node (ref "T10") (pin "4") (pinfunction "Pri_Dot_4") (pintype "passive"))
      (node (ref "U26") (pin "3") (pinfunction "RF1_3") (pintype "passive"))
    )
    (net (code "57") (name "Net-(U23-ENA)") (class "Default")
      (node (ref "C169") (pin "1") (pinfunction "1_1") (pintype "passive"))
      (node (ref "L55") (pin "1") (pinfunction "1_1") (pintype "passive"))
      (node (ref "U23") (pin "8") (pinfunction "ENA_8") (pintype "passive"))
      (node (ref "U23") (pin "9") (pinfunction "VCC_9") (pintype "passive"))
    )
    (net (code "58") (name "Net-(U23-RF1)") (class "Default")
      (node (ref "T1") (pin "1") (pinfunction "1_1") (pintype "passive"))
      (node (ref "U23") (pin "11") (pinfunction "RF1_11") (pintype "passive"))
    )
    (net (code "59") (name "Net-(U24-ENA)") (class "Default")
      (node (ref "C170") (pin "1") (pinfunction "1_1") (pintype "passive"))
      (node (ref "L56") (pin "1") (pinfunction "1_1") (pintype "passive"))
      (node (ref "U24") (pin "8") (pinfunction "ENA_8") (pintype "passive"))
      (node (ref "U24") (pin "9") (pinfunction "VCC_9") (pintype "passive"))
    )
    (net (code "60") (name "Net-(U24-RF1)") (class "Default")
      (node (ref "T3") (pin "1") (pinfunction "1_1") (pintype "passive"))
      (node (ref "U24") (pin "11") (pinfunction "RF1_11") (pintype "passive"))
    )
    (net (code "61") (name "Net-(U25-RF2)") (class "Default")
      (node (ref "T5") (pin "2") (pinfunction "2_2") (pintype "passive"))
      (node (ref "U25") (pin "9") (pinfunction "RF2_9") (pintype "passive"))
    )
    (net (code "62") (name "Net-(U25-RF3)") (class "Default")
      (node (ref "T6") (pin "1") (pinfunction "1_1") (pintype "passive"))
      (node (ref "U25") (pin "2") (pinfunction "RF3_2") (pintype "passive"))
    )
    (net (code "63") (name "Net-(U25-VDD)") (class "Default")
      (node (ref "C215") (pin "2") (pinfunction "2_2") (pintype "passive"))
      (node (ref "L71") (pin "1") (pinfunction "1_1") (pintype "passive"))
      (node (ref "U25") (pin "4") (pinfunction "VDD_4") (pintype "passive"))
    )
    (net (code "64") (name "Net-(U26-RF2)") (class "Default")
      (node (ref "T8") (pin "1") (pinfunction "1_1") (pintype "passive"))
      (node (ref "U26") (pin "9") (pinfunction "RF2_9") (pintype "passive"))
    )
    (net (code "65") (name "Net-(U26-RF3)") (class "Default")
      (node (ref "T9") (pin "1") (pinfunction "1_1") (pintype "passive"))
      (node (ref "U26") (pin "2") (pinfunction "RF3_2") (pintype "passive"))
    )
    (net (code "66") (name "Net-(U26-VDD)") (class "Default")
      (node (ref "C216") (pin "2") (pinfunction "2_2") (pintype "passive"))
      (node (ref "L72") (pin "1") (pinfunction "1_1") (pintype "passive"))
      (node (ref "U26") (pin "4") (pinfunction "VDD_4") (pintype "passive"))
    )
    (net (code "67") (name "unconnected-(U25-RF4-Pad10)") (class "Default")
      (node (ref "U25") (pin "10") (pinfunction "RF4_10") (pintype "passive+no_connect"))
    )
    (net (code "68") (name "unconnected-(U26-RF4-Pad10)") (class "Default")
      (node (ref "U26") (pin "10") (pinfunction "RF4_10") (pintype "passive+no_connect"))
    )
  )
)
